# GabozePocaio-Extension-Button-Audio.net
KiCad netlist of a schematic drawn in EAGLE
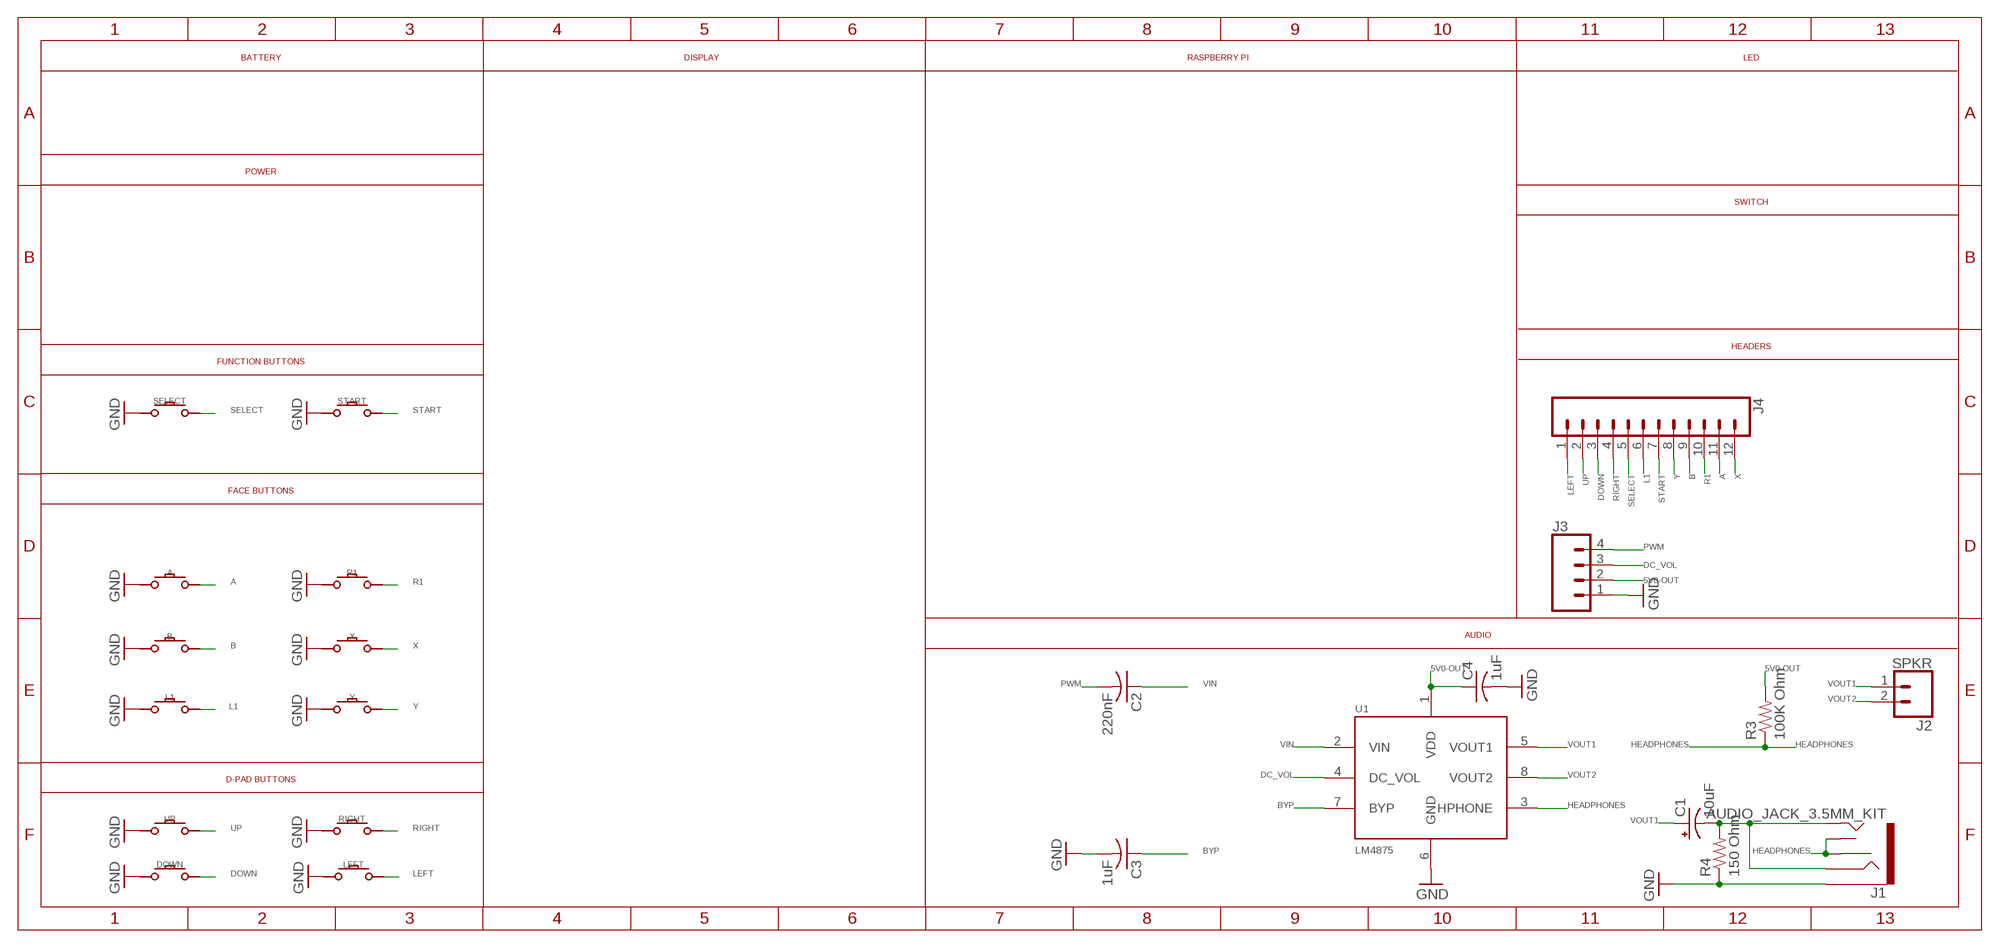
[diagram p0: schematic, sheet 1]

(export (version "E")
  (design (tool "Eeschema 10.0.6"))
  (components
    (comp (ref "A")
      (value "CONDUCTIVE_BUTTON")
      (footprint "eagle-import:CONDUCTIVE_BUTTON")
      (libsource (lib "eagle-import") (part "CONDUCTIVE_BUTTON"))
    )
    (comp (ref "B")
      (value "CONDUCTIVE_BUTTON")
      (footprint "eagle-import:CONDUCTIVE_BUTTON")
      (libsource (lib "eagle-import") (part "CONDUCTIVE_BUTTON"))
    )
    (comp (ref "C1")
      (value "10uF")
      (footprint "eagle-import:EIA3216")
      (libsource (lib "eagle-import") (part "10UF-POLAR-EIA3216-16V-10%(TANT)"))
    )
    (comp (ref "C2")
      (value "220nF")
      (footprint "eagle-import:C0805")
      (libsource (lib "eagle-import") (part "C-USC0805"))
    )
    (comp (ref "C3")
      (value "1uF")
      (footprint "eagle-import:C0805")
      (libsource (lib "eagle-import") (part "C-USC0805"))
    )
    (comp (ref "C4")
      (value "1uF")
      (footprint "eagle-import:C0805")
      (libsource (lib "eagle-import") (part "C-USC0805"))
    )
    (comp (ref "DOWN")
      (value "CONDUCTIVE_BUTTON")
      (footprint "eagle-import:CONDUCTIVE_BUTTON")
      (libsource (lib "eagle-import") (part "CONDUCTIVE_BUTTON"))
    )
    (comp (ref "J1")
      (value "AUDIO_JACK_3.5MM_KIT")
      (footprint "eagle-import:AUDIO-JACK-KIT")
      (libsource (lib "eagle-import") (part "AUDIO_JACK_3.5MM_KIT"))
    )
    (comp (ref "J2")
      (value "SPKR")
      (footprint "eagle-import:1X02")
      (libsource (lib "eagle-import") (part "CONN_02"))
    )
    (comp (ref "J3")
      (value "CONN_041X04_NO_SILK")
      (footprint "eagle-import:1X04_NO_SILK")
      (libsource (lib "eagle-import") (part "CONN_041X04_NO_SILK"))
    )
    (comp (ref "J4")
      (value "CONN_12NO_SILK")
      (footprint "eagle-import:1X12_NO_SILK")
      (libsource (lib "eagle-import") (part "CONN_12NO_SILK"))
    )
    (comp (ref "L1")
      (value "CONDUCTIVE_BUTTON_DRILL")
      (footprint "eagle-import:CONDUCTIVE_BUTTON_DRILL")
      (libsource (lib "eagle-import") (part "CONDUCTIVE_BUTTON_DRILL"))
    )
    (comp (ref "LEFT")
      (value "CONDUCTIVE_BUTTON")
      (footprint "eagle-import:CONDUCTIVE_BUTTON")
      (libsource (lib "eagle-import") (part "CONDUCTIVE_BUTTON"))
    )
    (comp (ref "R1")
      (value "CONDUCTIVE_BUTTON_DRILL")
      (footprint "eagle-import:CONDUCTIVE_BUTTON_DRILL")
      (libsource (lib "eagle-import") (part "CONDUCTIVE_BUTTON_DRILL"))
    )
    (comp (ref "R3")
      (value "100K Ohm")
      (footprint "eagle-import:R0805")
      (libsource (lib "eagle-import") (part "R-US_R0805"))
    )
    (comp (ref "R4")
      (value "150 Ohm")
      (footprint "eagle-import:R0805")
      (libsource (lib "eagle-import") (part "R-US_R0805"))
    )
    (comp (ref "RIGHT")
      (value "CONDUCTIVE_BUTTON")
      (footprint "eagle-import:CONDUCTIVE_BUTTON")
      (libsource (lib "eagle-import") (part "CONDUCTIVE_BUTTON"))
    )
    (comp (ref "SELECT")
      (value "CONDUCTIVE_BUTTON_STARTSELECT")
      (footprint "eagle-import:CONDUCTIVE_BUTTON_STARTSELECT")
      (libsource (lib "eagle-import") (part "CONDUCTIVE_BUTTON_STARTSELECT"))
    )
    (comp (ref "START")
      (value "CONDUCTIVE_BUTTON_STARTSELECT")
      (footprint "eagle-import:CONDUCTIVE_BUTTON_STARTSELECT")
      (libsource (lib "eagle-import") (part "CONDUCTIVE_BUTTON_STARTSELECT"))
    )
    (comp (ref "U1")
      (value "LM4875")
      (footprint "eagle-import:SOIC8")
      (libsource (lib "eagle-import") (part "LM4875"))
    )
    (comp (ref "UP")
      (value "CONDUCTIVE_BUTTON")
      (footprint "eagle-import:CONDUCTIVE_BUTTON")
      (libsource (lib "eagle-import") (part "CONDUCTIVE_BUTTON"))
    )
    (comp (ref "X")
      (value "CONDUCTIVE_BUTTON_DRILL")
      (footprint "eagle-import:CONDUCTIVE_BUTTON_DRILL")
      (libsource (lib "eagle-import") (part "CONDUCTIVE_BUTTON_DRILL"))
    )
    (comp (ref "Y")
      (value "CONDUCTIVE_BUTTON_DRILL")
      (footprint "eagle-import:CONDUCTIVE_BUTTON_DRILL")
      (libsource (lib "eagle-import") (part "CONDUCTIVE_BUTTON_DRILL"))
    )
  )
  (nets
    (net (code "1") (name "/5V0-OUT") (class "Default")
      (node (ref "C4") (pin "1") (pinfunction "1_1") (pintype "passive"))
      (node (ref "J3") (pin "2") (pinfunction "2_2") (pintype "passive"))
      (node (ref "R3") (pin "2") (pinfunction "2_2") (pintype "passive"))
      (node (ref "U1") (pin "1") (pinfunction "VDD_1") (pintype "power_in"))
    )
    (net (code "2") (name "/A") (class "Default")
      (node (ref "A") (pin "P$ACTIVE") (pinfunction "P$ACTIVE_P$ACTIVE") (pintype "bidirectional"))
      (node (ref "J4") (pin "11") (pinfunction "11_11") (pintype "passive"))
    )
    (net (code "3") (name "/B") (class "Default")
      (node (ref "B") (pin "P$ACTIVE") (pinfunction "P$ACTIVE_P$ACTIVE") (pintype "bidirectional"))
      (node (ref "J4") (pin "9") (pinfunction "9_9") (pintype "passive"))
    )
    (net (code "4") (name "/BYP") (class "Default")
      (node (ref "C3") (pin "1") (pinfunction "1_1") (pintype "passive"))
      (node (ref "U1") (pin "7") (pinfunction "BYP_7") (pintype "bidirectional"))
    )
    (net (code "5") (name "/DC_VOL") (class "Default")
      (node (ref "J3") (pin "3") (pinfunction "3_3") (pintype "passive"))
      (node (ref "U1") (pin "4") (pinfunction "DC_VOL_4") (pintype "input"))
    )
    (net (code "6") (name "/DOWN") (class "Default")
      (node (ref "DOWN") (pin "P$ACTIVE") (pinfunction "P$ACTIVE_P$ACTIVE") (pintype "bidirectional"))
      (node (ref "J4") (pin "3") (pinfunction "3_3") (pintype "passive"))
    )
    (net (code "7") (name "/HEADPHONES") (class "Default")
      (node (ref "J1") (pin "RSH") (pinfunction "RSH_RSH") (pintype "bidirectional"))
      (node (ref "J1") (pin "TSH") (pinfunction "TSH_TSH") (pintype "bidirectional"))
      (node (ref "R3") (pin "1") (pinfunction "1_1") (pintype "passive"))
      (node (ref "U1") (pin "3") (pinfunction "HPHONE_3") (pintype "input"))
    )
    (net (code "8") (name "/L1") (class "Default")
      (node (ref "J4") (pin "6") (pinfunction "6_6") (pintype "passive"))
      (node (ref "L1") (pin "P$ACTIVE") (pinfunction "P$ACTIVE_P$ACTIVE") (pintype "bidirectional"))
    )
    (net (code "9") (name "/LEFT") (class "Default")
      (node (ref "J4") (pin "1") (pinfunction "1_1") (pintype "passive"))
      (node (ref "LEFT") (pin "P$ACTIVE") (pinfunction "P$ACTIVE_P$ACTIVE") (pintype "bidirectional"))
    )
    (net (code "10") (name "/PWM") (class "Default")
      (node (ref "C2") (pin "2") (pinfunction "2_2") (pintype "passive"))
      (node (ref "J3") (pin "4") (pinfunction "4_4") (pintype "passive"))
    )
    (net (code "11") (name "/R1") (class "Default")
      (node (ref "J4") (pin "10") (pinfunction "10_10") (pintype "passive"))
      (node (ref "R1") (pin "P$ACTIVE") (pinfunction "P$ACTIVE_P$ACTIVE") (pintype "bidirectional"))
    )
    (net (code "12") (name "/RIGHT") (class "Default")
      (node (ref "J4") (pin "4") (pinfunction "4_4") (pintype "passive"))
      (node (ref "RIGHT") (pin "P$ACTIVE") (pinfunction "P$ACTIVE_P$ACTIVE") (pintype "bidirectional"))
    )
    (net (code "13") (name "/SELECT") (class "Default")
      (node (ref "J4") (pin "5") (pinfunction "5_5") (pintype "passive"))
      (node (ref "SELECT") (pin "P$ACTIVE") (pinfunction "P$ACTIVE_P$ACTIVE") (pintype "bidirectional"))
    )
    (net (code "14") (name "/START") (class "Default")
      (node (ref "J4") (pin "7") (pinfunction "7_7") (pintype "passive"))
      (node (ref "START") (pin "P$ACTIVE") (pinfunction "P$ACTIVE_P$ACTIVE") (pintype "bidirectional"))
    )
    (net (code "15") (name "/UP") (class "Default")
      (node (ref "J4") (pin "2") (pinfunction "2_2") (pintype "passive"))
      (node (ref "UP") (pin "P$ACTIVE") (pinfunction "P$ACTIVE_P$ACTIVE") (pintype "bidirectional"))
    )
    (net (code "16") (name "/VIN") (class "Default")
      (node (ref "C2") (pin "1") (pinfunction "1_1") (pintype "passive"))
      (node (ref "U1") (pin "2") (pinfunction "VIN_2") (pintype "input"))
    )
    (net (code "17") (name "/VOUT1") (class "Default")
      (node (ref "C1") (pin "+") (pinfunction "+_+") (pintype "passive"))
      (node (ref "J2") (pin "1") (pinfunction "1_1") (pintype "passive"))
      (node (ref "U1") (pin "5") (pinfunction "VOUT1_5") (pintype "output"))
    )
    (net (code "18") (name "/VOUT2") (class "Default")
      (node (ref "J2") (pin "2") (pinfunction "2_2") (pintype "passive"))
      (node (ref "U1") (pin "8") (pinfunction "VOUT2_8") (pintype "output"))
    )
    (net (code "19") (name "/X") (class "Default")
      (node (ref "J4") (pin "12") (pinfunction "12_12") (pintype "passive"))
      (node (ref "X") (pin "P$ACTIVE") (pinfunction "P$ACTIVE_P$ACTIVE") (pintype "bidirectional"))
    )
    (net (code "20") (name "/Y") (class "Default")
      (node (ref "J4") (pin "8") (pinfunction "8_8") (pintype "passive"))
      (node (ref "Y") (pin "P$ACTIVE") (pinfunction "P$ACTIVE_P$ACTIVE") (pintype "bidirectional"))
    )
    (net (code "21") (name "GND") (class "Default")
      (node (ref "A") (pin "P$GND") (pinfunction "P$GND_P$GND") (pintype "bidirectional"))
      (node (ref "B") (pin "P$GND") (pinfunction "P$GND_P$GND") (pintype "bidirectional"))
      (node (ref "C3") (pin "2") (pinfunction "2_2") (pintype "passive"))
      (node (ref "C4") (pin "2") (pinfunction "2_2") (pintype "passive"))
      (node (ref "DOWN") (pin "P$GND") (pinfunction "P$GND_P$GND") (pintype "bidirectional"))
      (node (ref "J1") (pin "SLEEVE") (pinfunction "SLEEVE_SLEEVE") (pintype "bidirectional"))
      (node (ref "J3") (pin "1") (pinfunction "1_1") (pintype "passive"))
      (node (ref "L1") (pin "P$GND") (pinfunction "P$GND_P$GND") (pintype "bidirectional"))
      (node (ref "LEFT") (pin "P$GND") (pinfunction "P$GND_P$GND") (pintype "bidirectional"))
      (node (ref "R1") (pin "P$GND") (pinfunction "P$GND_P$GND") (pintype "bidirectional"))
      (node (ref "R4") (pin "1") (pinfunction "1_1") (pintype "passive"))
      (node (ref "RIGHT") (pin "P$GND") (pinfunction "P$GND_P$GND") (pintype "bidirectional"))
      (node (ref "SELECT") (pin "P$GND") (pinfunction "P$GND_P$GND") (pintype "bidirectional"))
      (node (ref "START") (pin "P$GND") (pinfunction "P$GND_P$GND") (pintype "bidirectional"))
      (node (ref "U1") (pin "6") (pinfunction "GND_6") (pintype "power_in"))
      (node (ref "UP") (pin "P$GND") (pinfunction "P$GND_P$GND") (pintype "bidirectional"))
      (node (ref "X") (pin "P$GND") (pinfunction "P$GND_P$GND") (pintype "bidirectional"))
      (node (ref "Y") (pin "P$GND") (pinfunction "P$GND_P$GND") (pintype "bidirectional"))
    )
    (net (code "22") (name "Net-(C1-Pad-)") (class "Default")
      (node (ref "C1") (pin "-") (pinfunction "-_-") (pintype "passive"))
      (node (ref "J1") (pin "RING") (pinfunction "RING_RING") (pintype "bidirectional"))
      (node (ref "J1") (pin "TIP") (pinfunction "TIP_TIP") (pintype "bidirectional"))
      (node (ref "R4") (pin "2") (pinfunction "2_2") (pintype "passive"))
    )
  )
)
